# power_load.net
KiCad netlist of a schematic drawn in EAGLE
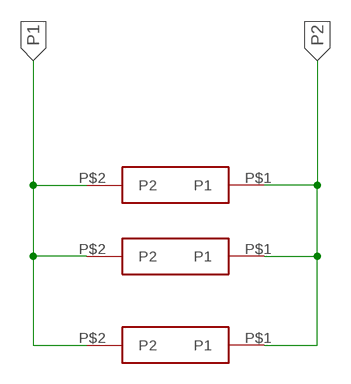
[diagram p0: schematic, sheet 1]

(export (version "E")
  (design (tool "Eeschema 10.0.6"))
  (components
    (comp (ref "U$1")
      (value "ARCOL_10W")
      (footprint "eagle-import:10W_ARCOL")
      (libsource (lib "eagle-import") (part "ARCOL_10W"))
    )
    (comp (ref "U$2")
      (value "ARCOL_10W")
      (footprint "eagle-import:10W_ARCOL")
      (libsource (lib "eagle-import") (part "ARCOL_10W"))
    )
    (comp (ref "U$3")
      (value "ARCOL_10W")
      (footprint "eagle-import:10W_ARCOL")
      (libsource (lib "eagle-import") (part "ARCOL_10W"))
    )
  )
  (nets
    (net (code "1") (name "P1") (class "Default")
      (node (ref "U$1") (pin "P$2") (pinfunction "P2_P$2") (pintype "bidirectional"))
      (node (ref "U$2") (pin "P$2") (pinfunction "P2_P$2") (pintype "bidirectional"))
      (node (ref "U$3") (pin "P$2") (pinfunction "P2_P$2") (pintype "bidirectional"))
    )
    (net (code "2") (name "P2") (class "Default")
      (node (ref "U$1") (pin "P$1") (pinfunction "P1_P$1") (pintype "bidirectional"))
      (node (ref "U$2") (pin "P$1") (pinfunction "P1_P$1") (pintype "bidirectional"))
      (node (ref "U$3") (pin "P$1") (pinfunction "P1_P$1") (pintype "bidirectional"))
    )
  )
)
